# MB1-MCU-r1_0.net
KiCad netlist of a schematic drawn in Altium Designer
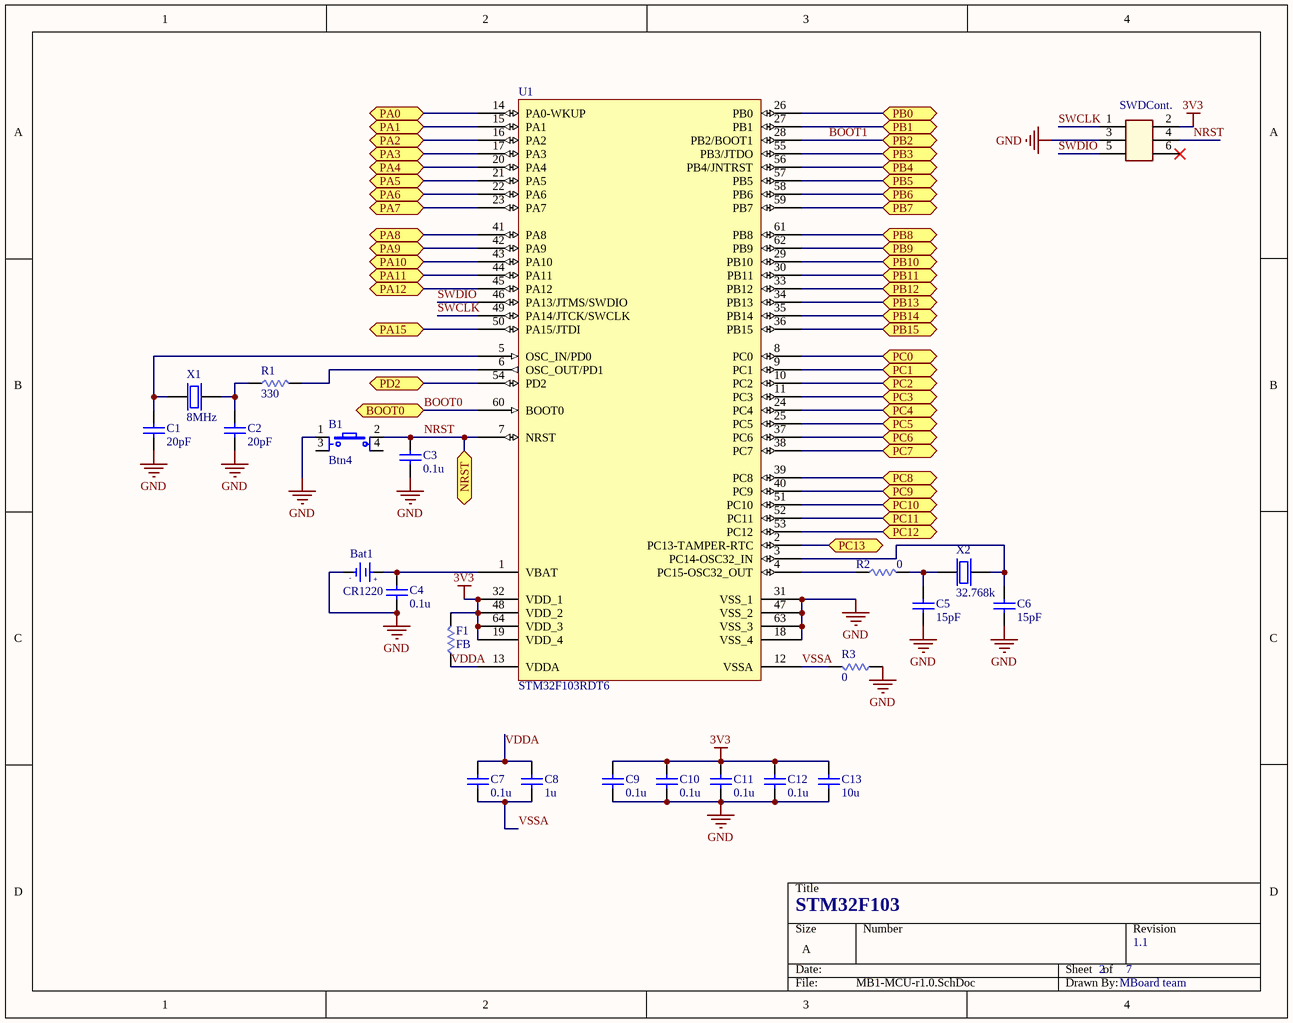
[diagram p0: MB1-MCU-r1.0.SchDoc]

(export (version "E")
  (design (tool "Eeschema 10.0.6"))
  (components
    (comp (ref "B1")
      (value "Btn4")
      (footprint "Horizon_SW_4pin_rectangular")
      (libsource (lib "MyLib") (part "Btn4"))
    )
    (comp (ref "Bat1")
      (value "CR1220")
      (footprint "PIN3VSOCKET-SMD")
      (description "Battery 3VDC")
      (fields (field (name "Comment") "PIN 3V"))
      (libsource (lib "VioletofSun") (part "PIN 3V"))
    )
    (comp (ref "C1")
      (value "20pF")
      (footprint "SM_0805_C_CERAMIC")
      (description "Non-polarity ceramic capacitor")
      (fields (field (name "Comment") "CAP Ceramic") (field (name "PUBLISHER") "Altium Limited"))
      (libsource (lib "HLib_schematic_lib") (part "CAP Ceramic"))
    )
    (comp (ref "C2")
      (value "20pF")
      (footprint "SM_0805_C_CERAMIC")
      (description "Non-polarity ceramic capacitor")
      (fields (field (name "Comment") "CAP Ceramic") (field (name "PUBLISHER") "Altium Limited"))
      (libsource (lib "HLib_schematic_lib") (part "CAP Ceramic"))
    )
    (comp (ref "C3")
      (value "0.1u")
      (footprint "SM_0805_C_CERAMIC")
      (description "Non-polarity ceramic capacitor")
      (fields (field (name "Comment") "CAP Ceramic") (field (name "PUBLISHER") "Altium Limited"))
      (libsource (lib "HLib_schematic_lib") (part "CAP Ceramic"))
    )
    (comp (ref "C4")
      (value "0.1u")
      (footprint "SM_0805_C_CERAMIC")
      (description "Non-polarity ceramic capacitor")
      (fields (field (name "Comment") "CAP Ceramic") (field (name "PUBLISHER") "Altium Limited"))
      (libsource (lib "HLib_schematic_lib") (part "CAP Ceramic"))
    )
    (comp (ref "C5")
      (value "15pF")
      (footprint "SM_0805_C_CERAMIC")
      (description "Non-polarity ceramic capacitor")
      (fields (field (name "Comment") "CAP Ceramic") (field (name "PUBLISHER") "Altium Limited"))
      (libsource (lib "HLib_schematic_lib") (part "CAP Ceramic"))
    )
    (comp (ref "C6")
      (value "15pF")
      (footprint "SM_0805_C_CERAMIC")
      (description "Non-polarity ceramic capacitor")
      (fields (field (name "Comment") "CAP Ceramic") (field (name "PUBLISHER") "Altium Limited"))
      (libsource (lib "HLib_schematic_lib") (part "CAP Ceramic"))
    )
    (comp (ref "C7")
      (value "0.1u")
      (footprint "SM_0805_C_CERAMIC")
      (description "Non-polarity ceramic capacitor")
      (fields (field (name "Comment") "CAP Ceramic") (field (name "PUBLISHER") "Altium Limited"))
      (libsource (lib "HLib_schematic_lib") (part "CAP Ceramic"))
    )
    (comp (ref "C8")
      (value "1u")
      (footprint "SM_0805_C_CERAMIC")
      (description "Non-polarity ceramic capacitor")
      (fields (field (name "Comment") "CAP Ceramic") (field (name "PUBLISHER") "Altium Limited"))
      (libsource (lib "HLib_schematic_lib") (part "CAP Ceramic"))
    )
    (comp (ref "C9")
      (value "0.1u")
      (footprint "SM_0805_C_CERAMIC")
      (description "Non-polarity ceramic capacitor")
      (fields (field (name "Comment") "CAP Ceramic") (field (name "PUBLISHER") "Altium Limited"))
      (libsource (lib "HLib_schematic_lib") (part "CAP Ceramic"))
    )
    (comp (ref "C10")
      (value "0.1u")
      (footprint "SM_0805_C_CERAMIC")
      (description "Non-polarity ceramic capacitor")
      (fields (field (name "Comment") "CAP Ceramic") (field (name "PUBLISHER") "Altium Limited"))
      (libsource (lib "HLib_schematic_lib") (part "CAP Ceramic"))
    )
    (comp (ref "C11")
      (value "0.1u")
      (footprint "SM_0805_C_CERAMIC")
      (description "Non-polarity ceramic capacitor")
      (fields (field (name "Comment") "CAP Ceramic") (field (name "PUBLISHER") "Altium Limited"))
      (libsource (lib "HLib_schematic_lib") (part "CAP Ceramic"))
    )
    (comp (ref "C12")
      (value "0.1u")
      (footprint "SM_0805_C_CERAMIC")
      (description "Non-polarity ceramic capacitor")
      (fields (field (name "Comment") "CAP Ceramic") (field (name "PUBLISHER") "Altium Limited"))
      (libsource (lib "HLib_schematic_lib") (part "CAP Ceramic"))
    )
    (comp (ref "C13")
      (value "10u")
      (footprint "SM_0805_C_CERAMIC")
      (description "Non-polarity ceramic capacitor")
      (fields (field (name "Comment") "CAP Ceramic") (field (name "PUBLISHER") "Altium Limited"))
      (libsource (lib "HLib_schematic_lib") (part "CAP Ceramic"))
    )
    (comp (ref "F1")
      (value "FB")
      (footprint "SM_0805_R")
      (description "Resistor")
      (fields (field (name "Comment") "Ferrite bead") (field (name "PUBLISHER") "Altium Limited"))
      (libsource (lib "HLib_schematic_lib") (part "R"))
    )
    (comp (ref "R1")
      (value "330")
      (footprint "SM_0805_R")
      (description "Resistor")
      (fields (field (name "PUBLISHER") "Altium Limited"))
      (libsource (lib "HLib_schematic_lib") (part "R"))
    )
    (comp (ref "R2")
      (value "0")
      (footprint "SM_0805_R")
      (description "Resistor")
      (fields (field (name "PUBLISHER") "Altium Limited"))
      (libsource (lib "HLib_schematic_lib") (part "R"))
    )
    (comp (ref "R3")
      (value "0")
      (footprint "SM_0805_R")
      (description "Resistor")
      (fields (field (name "PUBLISHER") "Altium Limited"))
      (libsource (lib "HLib_schematic_lib") (part "R"))
    )
    (comp (ref "SWDCont.")
      (value "SWD")
      (footprint "Hed3x2-RA")
      (description "Header, 3-pins/row, double row,")
      (libsource (lib "HLib_connector_sch") (part "HD_3x2"))
    )
    (comp (ref "U1")
      (value "STM32F103RDT6")
      (footprint "LQFP64_L")
      (description "STM32 ARM-based 32-bit MCU with 128 Kbytes Flash, 64-pin LQFP, Industrial Temperature")
      (fields (field (name "PUBLISHER") "Altium Limited"))
      (libsource (lib "ST Microcontroller 32-Bit STM32") (part "STM32F103RBT6"))
    )
    (comp (ref "X1")
      (value "8MHz")
      (footprint "HC49/US-SMD")
      (fields (field (name "Comment") "Crystal 2 pin."))
      (libsource (lib "MyLib") (part "XT2"))
    )
    (comp (ref "X2")
      (value "32.768k")
      (footprint "XT32-LOB")
      (fields (field (name "Comment") "Crystal 32.768 k"))
      (libsource (lib "MyLib") (part "XT32k"))
    )
  )
  (nets
    (net (code "1") (name "/BOOT0") (class "Default")
      (node (ref "U1") (pin "60") (pinfunction "BOOT0_60") (pintype "input"))
    )
    (net (code "2") (name "/BOOT1") (class "Default")
      (node (ref "U1") (pin "28") (pinfunction "PB2/BOOT1_28") (pintype "bidirectional"))
    )
    (net (code "3") (name "/NRST") (class "Default")
      (node (ref "B1") (pin "2") (pinfunction "Tab_2") (pintype "passive"))
      (node (ref "C3") (pin "2") (pinfunction "2_2") (pintype "passive"))
      (node (ref "SWDCont.") (pin "4") (pinfunction "4_4") (pintype "passive"))
      (node (ref "U1") (pin "7") (pinfunction "NRST_7") (pintype "bidirectional"))
    )
    (net (code "4") (name "/PA0") (class "Default")
      (node (ref "U1") (pin "14") (pinfunction "PA0-WKUP_14") (pintype "bidirectional"))
    )
    (net (code "5") (name "/PA1") (class "Default")
      (node (ref "U1") (pin "15") (pinfunction "PA1_15") (pintype "bidirectional"))
    )
    (net (code "6") (name "/PA2") (class "Default")
      (node (ref "U1") (pin "16") (pinfunction "PA2_16") (pintype "bidirectional"))
    )
    (net (code "7") (name "/PA3") (class "Default")
      (node (ref "U1") (pin "17") (pinfunction "PA3_17") (pintype "bidirectional"))
    )
    (net (code "8") (name "/PA4") (class "Default")
      (node (ref "U1") (pin "20") (pinfunction "PA4_20") (pintype "bidirectional"))
    )
    (net (code "9") (name "/PA5") (class "Default")
      (node (ref "U1") (pin "21") (pinfunction "PA5_21") (pintype "bidirectional"))
    )
    (net (code "10") (name "/PA6") (class "Default")
      (node (ref "U1") (pin "22") (pinfunction "PA6_22") (pintype "bidirectional"))
    )
    (net (code "11") (name "/PA7") (class "Default")
      (node (ref "U1") (pin "23") (pinfunction "PA7_23") (pintype "bidirectional"))
    )
    (net (code "12") (name "/PA8") (class "Default")
      (node (ref "U1") (pin "41") (pinfunction "PA8_41") (pintype "bidirectional"))
    )
    (net (code "13") (name "/PA9") (class "Default")
      (node (ref "U1") (pin "42") (pinfunction "PA9_42") (pintype "bidirectional"))
    )
    (net (code "14") (name "/PA10") (class "Default")
      (node (ref "U1") (pin "43") (pinfunction "PA10_43") (pintype "bidirectional"))
    )
    (net (code "15") (name "/PA11") (class "Default")
      (node (ref "U1") (pin "44") (pinfunction "PA11_44") (pintype "bidirectional"))
    )
    (net (code "16") (name "/PA12") (class "Default")
      (node (ref "U1") (pin "45") (pinfunction "PA12_45") (pintype "bidirectional"))
    )
    (net (code "17") (name "/PA15") (class "Default")
      (node (ref "U1") (pin "50") (pinfunction "PA15/JTDI_50") (pintype "bidirectional"))
    )
    (net (code "18") (name "/PB0") (class "Default")
      (node (ref "U1") (pin "26") (pinfunction "PB0_26") (pintype "bidirectional"))
    )
    (net (code "19") (name "/PB1") (class "Default")
      (node (ref "U1") (pin "27") (pinfunction "PB1_27") (pintype "bidirectional"))
    )
    (net (code "20") (name "/PB3") (class "Default")
      (node (ref "U1") (pin "55") (pinfunction "PB3/JTDO_55") (pintype "bidirectional"))
    )
    (net (code "21") (name "/PB4") (class "Default")
      (node (ref "U1") (pin "56") (pinfunction "PB4/JNTRST_56") (pintype "bidirectional"))
    )
    (net (code "22") (name "/PB5") (class "Default")
      (node (ref "U1") (pin "57") (pinfunction "PB5_57") (pintype "bidirectional"))
    )
    (net (code "23") (name "/PB6") (class "Default")
      (node (ref "U1") (pin "58") (pinfunction "PB6_58") (pintype "bidirectional"))
    )
    (net (code "24") (name "/PB7") (class "Default")
      (node (ref "U1") (pin "59") (pinfunction "PB7_59") (pintype "bidirectional"))
    )
    (net (code "25") (name "/PB8") (class "Default")
      (node (ref "U1") (pin "61") (pinfunction "PB8_61") (pintype "bidirectional"))
    )
    (net (code "26") (name "/PB9") (class "Default")
      (node (ref "U1") (pin "62") (pinfunction "PB9_62") (pintype "bidirectional"))
    )
    (net (code "27") (name "/PB10") (class "Default")
      (node (ref "U1") (pin "29") (pinfunction "PB10_29") (pintype "bidirectional"))
    )
    (net (code "28") (name "/PB11") (class "Default")
      (node (ref "U1") (pin "30") (pinfunction "PB11_30") (pintype "bidirectional"))
    )
    (net (code "29") (name "/PB12") (class "Default")
      (node (ref "U1") (pin "33") (pinfunction "PB12_33") (pintype "bidirectional"))
    )
    (net (code "30") (name "/PB13") (class "Default")
      (node (ref "U1") (pin "34") (pinfunction "PB13_34") (pintype "bidirectional"))
    )
    (net (code "31") (name "/PB14") (class "Default")
      (node (ref "U1") (pin "35") (pinfunction "PB14_35") (pintype "bidirectional"))
    )
    (net (code "32") (name "/PB15") (class "Default")
      (node (ref "U1") (pin "36") (pinfunction "PB15_36") (pintype "bidirectional"))
    )
    (net (code "33") (name "/PC0") (class "Default")
      (node (ref "U1") (pin "8") (pinfunction "PC0_8") (pintype "bidirectional"))
    )
    (net (code "34") (name "/PC1") (class "Default")
      (node (ref "U1") (pin "9") (pinfunction "PC1_9") (pintype "bidirectional"))
    )
    (net (code "35") (name "/PC2") (class "Default")
      (node (ref "U1") (pin "10") (pinfunction "PC2_10") (pintype "bidirectional"))
    )
    (net (code "36") (name "/PC3") (class "Default")
      (node (ref "U1") (pin "11") (pinfunction "PC3_11") (pintype "bidirectional"))
    )
    (net (code "37") (name "/PC4") (class "Default")
      (node (ref "U1") (pin "24") (pinfunction "PC4_24") (pintype "bidirectional"))
    )
    (net (code "38") (name "/PC5") (class "Default")
      (node (ref "U1") (pin "25") (pinfunction "PC5_25") (pintype "bidirectional"))
    )
    (net (code "39") (name "/PC6") (class "Default")
      (node (ref "U1") (pin "37") (pinfunction "PC6_37") (pintype "bidirectional"))
    )
    (net (code "40") (name "/PC7") (class "Default")
      (node (ref "U1") (pin "38") (pinfunction "PC7_38") (pintype "bidirectional"))
    )
    (net (code "41") (name "/PC8") (class "Default")
      (node (ref "U1") (pin "39") (pinfunction "PC8_39") (pintype "bidirectional"))
    )
    (net (code "42") (name "/PC9") (class "Default")
      (node (ref "U1") (pin "40") (pinfunction "PC9_40") (pintype "bidirectional"))
    )
    (net (code "43") (name "/PC10") (class "Default")
      (node (ref "U1") (pin "51") (pinfunction "PC10_51") (pintype "bidirectional"))
    )
    (net (code "44") (name "/PC11") (class "Default")
      (node (ref "U1") (pin "52") (pinfunction "PC11_52") (pintype "bidirectional"))
    )
    (net (code "45") (name "/PC12") (class "Default")
      (node (ref "U1") (pin "53") (pinfunction "PC12_53") (pintype "bidirectional"))
    )
    (net (code "46") (name "/PC13") (class "Default")
      (node (ref "U1") (pin "2") (pinfunction "PC13-TAMPER-RTC_2") (pintype "bidirectional"))
    )
    (net (code "47") (name "/PD2") (class "Default")
      (node (ref "U1") (pin "54") (pinfunction "PD2_54") (pintype "bidirectional"))
    )
    (net (code "48") (name "/SWCLK") (class "Default")
      (node (ref "SWDCont.") (pin "1") (pinfunction "1_1") (pintype "passive"))
      (node (ref "U1") (pin "49") (pinfunction "PA14/JTCK/SWCLK_49") (pintype "bidirectional"))
    )
    (net (code "49") (name "/SWDIO") (class "Default")
      (node (ref "SWDCont.") (pin "5") (pinfunction "5_5") (pintype "passive"))
      (node (ref "U1") (pin "46") (pinfunction "PA13/JTMS/SWDIO_46") (pintype "bidirectional"))
    )
    (net (code "50") (name "/VDDA") (class "Default")
      (node (ref "C7") (pin "2") (pinfunction "2_2") (pintype "passive"))
      (node (ref "C8") (pin "2") (pinfunction "2_2") (pintype "passive"))
      (node (ref "F1") (pin "1") (pinfunction "1_1") (pintype "passive"))
      (node (ref "U1") (pin "13") (pinfunction "VDDA_13") (pintype "power_in"))
    )
    (net (code "51") (name "/VSSA") (class "Default")
      (node (ref "C7") (pin "1") (pinfunction "1_1") (pintype "passive"))
      (node (ref "C8") (pin "1") (pinfunction "1_1") (pintype "passive"))
      (node (ref "R3") (pin "2") (pinfunction "2_2") (pintype "passive"))
      (node (ref "U1") (pin "12") (pinfunction "VSSA_12") (pintype "power_in"))
    )
    (net (code "52") (name "3V3") (class "Default")
      (node (ref "C10") (pin "2") (pinfunction "2_2") (pintype "passive"))
      (node (ref "C11") (pin "2") (pinfunction "2_2") (pintype "passive"))
      (node (ref "C12") (pin "2") (pinfunction "2_2") (pintype "passive"))
      (node (ref "C13") (pin "2") (pinfunction "2_2") (pintype "passive"))
      (node (ref "C9") (pin "2") (pinfunction "2_2") (pintype "passive"))
      (node (ref "F1") (pin "2") (pinfunction "2_2") (pintype "passive"))
      (node (ref "SWDCont.") (pin "2") (pinfunction "2_2") (pintype "passive"))
      (node (ref "U1") (pin "19") (pinfunction "VDD_4_19") (pintype "power_in"))
      (node (ref "U1") (pin "32") (pinfunction "VDD_1_32") (pintype "power_in"))
      (node (ref "U1") (pin "48") (pinfunction "VDD_2_48") (pintype "power_in"))
      (node (ref "U1") (pin "64") (pinfunction "VDD_3_64") (pintype "power_in"))
    )
    (net (code "53") (name "GND") (class "Default")
      (node (ref "B1") (pin "1") (pinfunction "Tab_1") (pintype "passive"))
      (node (ref "Bat1") (pin "2") (pinfunction "GND_2") (pintype "passive"))
      (node (ref "C1") (pin "1") (pinfunction "1_1") (pintype "passive"))
      (node (ref "C10") (pin "1") (pinfunction "1_1") (pintype "passive"))
      (node (ref "C11") (pin "1") (pinfunction "1_1") (pintype "passive"))
      (node (ref "C12") (pin "1") (pinfunction "1_1") (pintype "passive"))
      (node (ref "C13") (pin "1") (pinfunction "1_1") (pintype "passive"))
      (node (ref "C2") (pin "1") (pinfunction "1_1") (pintype "passive"))
      (node (ref "C3") (pin "1") (pinfunction "1_1") (pintype "passive"))
      (node (ref "C4") (pin "1") (pinfunction "1_1") (pintype "passive"))
      (node (ref "C5") (pin "1") (pinfunction "1_1") (pintype "passive"))
      (node (ref "C6") (pin "1") (pinfunction "1_1") (pintype "passive"))
      (node (ref "C9") (pin "1") (pinfunction "1_1") (pintype "passive"))
      (node (ref "R3") (pin "1") (pinfunction "1_1") (pintype "passive"))
      (node (ref "SWDCont.") (pin "3") (pinfunction "3_3") (pintype "passive"))
      (node (ref "U1") (pin "18") (pinfunction "VSS_4_18") (pintype "power_in"))
      (node (ref "U1") (pin "31") (pinfunction "VSS_1_31") (pintype "power_in"))
      (node (ref "U1") (pin "47") (pinfunction "VSS_2_47") (pintype "power_in"))
      (node (ref "U1") (pin "63") (pinfunction "VSS_3_63") (pintype "power_in"))
    )
    (net (code "54") (name "Net-(Bat1-+3V)") (class "Default")
      (node (ref "Bat1") (pin "1") (pinfunction "+3V_1") (pintype "passive"))
      (node (ref "C4") (pin "2") (pinfunction "2_2") (pintype "passive"))
      (node (ref "U1") (pin "1") (pinfunction "VBAT_1") (pintype "power_in"))
    )
    (net (code "55") (name "Net-(U1-OSC_IN{slash}PD0)") (class "Default")
      (node (ref "C1") (pin "2") (pinfunction "2_2") (pintype "passive"))
      (node (ref "U1") (pin "5") (pinfunction "OSC_IN/PD0_5") (pintype "input"))
      (node (ref "X1") (pin "1") (pinfunction "Xin_1") (pintype "passive"))
    )
    (net (code "56") (name "Net-(U1-OSC_OUT{slash}PD1)") (class "Default")
      (node (ref "R1") (pin "2") (pinfunction "2_2") (pintype "passive"))
      (node (ref "U1") (pin "6") (pinfunction "OSC_OUT/PD1_6") (pintype "output"))
    )
    (net (code "57") (name "Net-(U1-PC14-OSC32_IN)") (class "Default")
      (node (ref "C6") (pin "2") (pinfunction "2_2") (pintype "passive"))
      (node (ref "U1") (pin "3") (pinfunction "PC14-OSC32_IN_3") (pintype "bidirectional"))
      (node (ref "X2") (pin "2") (pinfunction "Xout_2") (pintype "passive"))
    )
    (net (code "58") (name "Net-(U1-PC15-OSC32_OUT)") (class "Default")
      (node (ref "R2") (pin "1") (pinfunction "1_1") (pintype "passive"))
      (node (ref "U1") (pin "4") (pinfunction "PC15-OSC32_OUT_4") (pintype "bidirectional"))
    )
    (net (code "59") (name "Net-(X1-Xout)") (class "Default")
      (node (ref "C2") (pin "2") (pinfunction "2_2") (pintype "passive"))
      (node (ref "R1") (pin "1") (pinfunction "1_1") (pintype "passive"))
      (node (ref "X1") (pin "2") (pinfunction "Xout_2") (pintype "passive"))
    )
    (net (code "60") (name "Net-(X2-Xin)") (class "Default")
      (node (ref "C5") (pin "2") (pinfunction "2_2") (pintype "passive"))
      (node (ref "R2") (pin "2") (pinfunction "2_2") (pintype "passive"))
      (node (ref "X2") (pin "1") (pinfunction "Xin_1") (pintype "passive"))
    )
    (net (code "61") (name "unconnected-(B1-Tab-Pad3)") (class "Default")
      (node (ref "B1") (pin "3") (pinfunction "Tab_3") (pintype "passive"))
    )
    (net (code "62") (name "unconnected-(B1-Tab-Pad4)") (class "Default")
      (node (ref "B1") (pin "4") (pinfunction "Tab_4") (pintype "passive"))
    )
    (net (code "63") (name "unconnected-(SWDCont.-Pad6)") (class "Default")
      (node (ref "SWDCont.") (pin "6") (pinfunction "6_6") (pintype "passive+no_connect"))
    )
  )
)
